# openSX70_ALADDIN_V391_20180125C.net
KiCad netlist of a schematic drawn in EAGLE
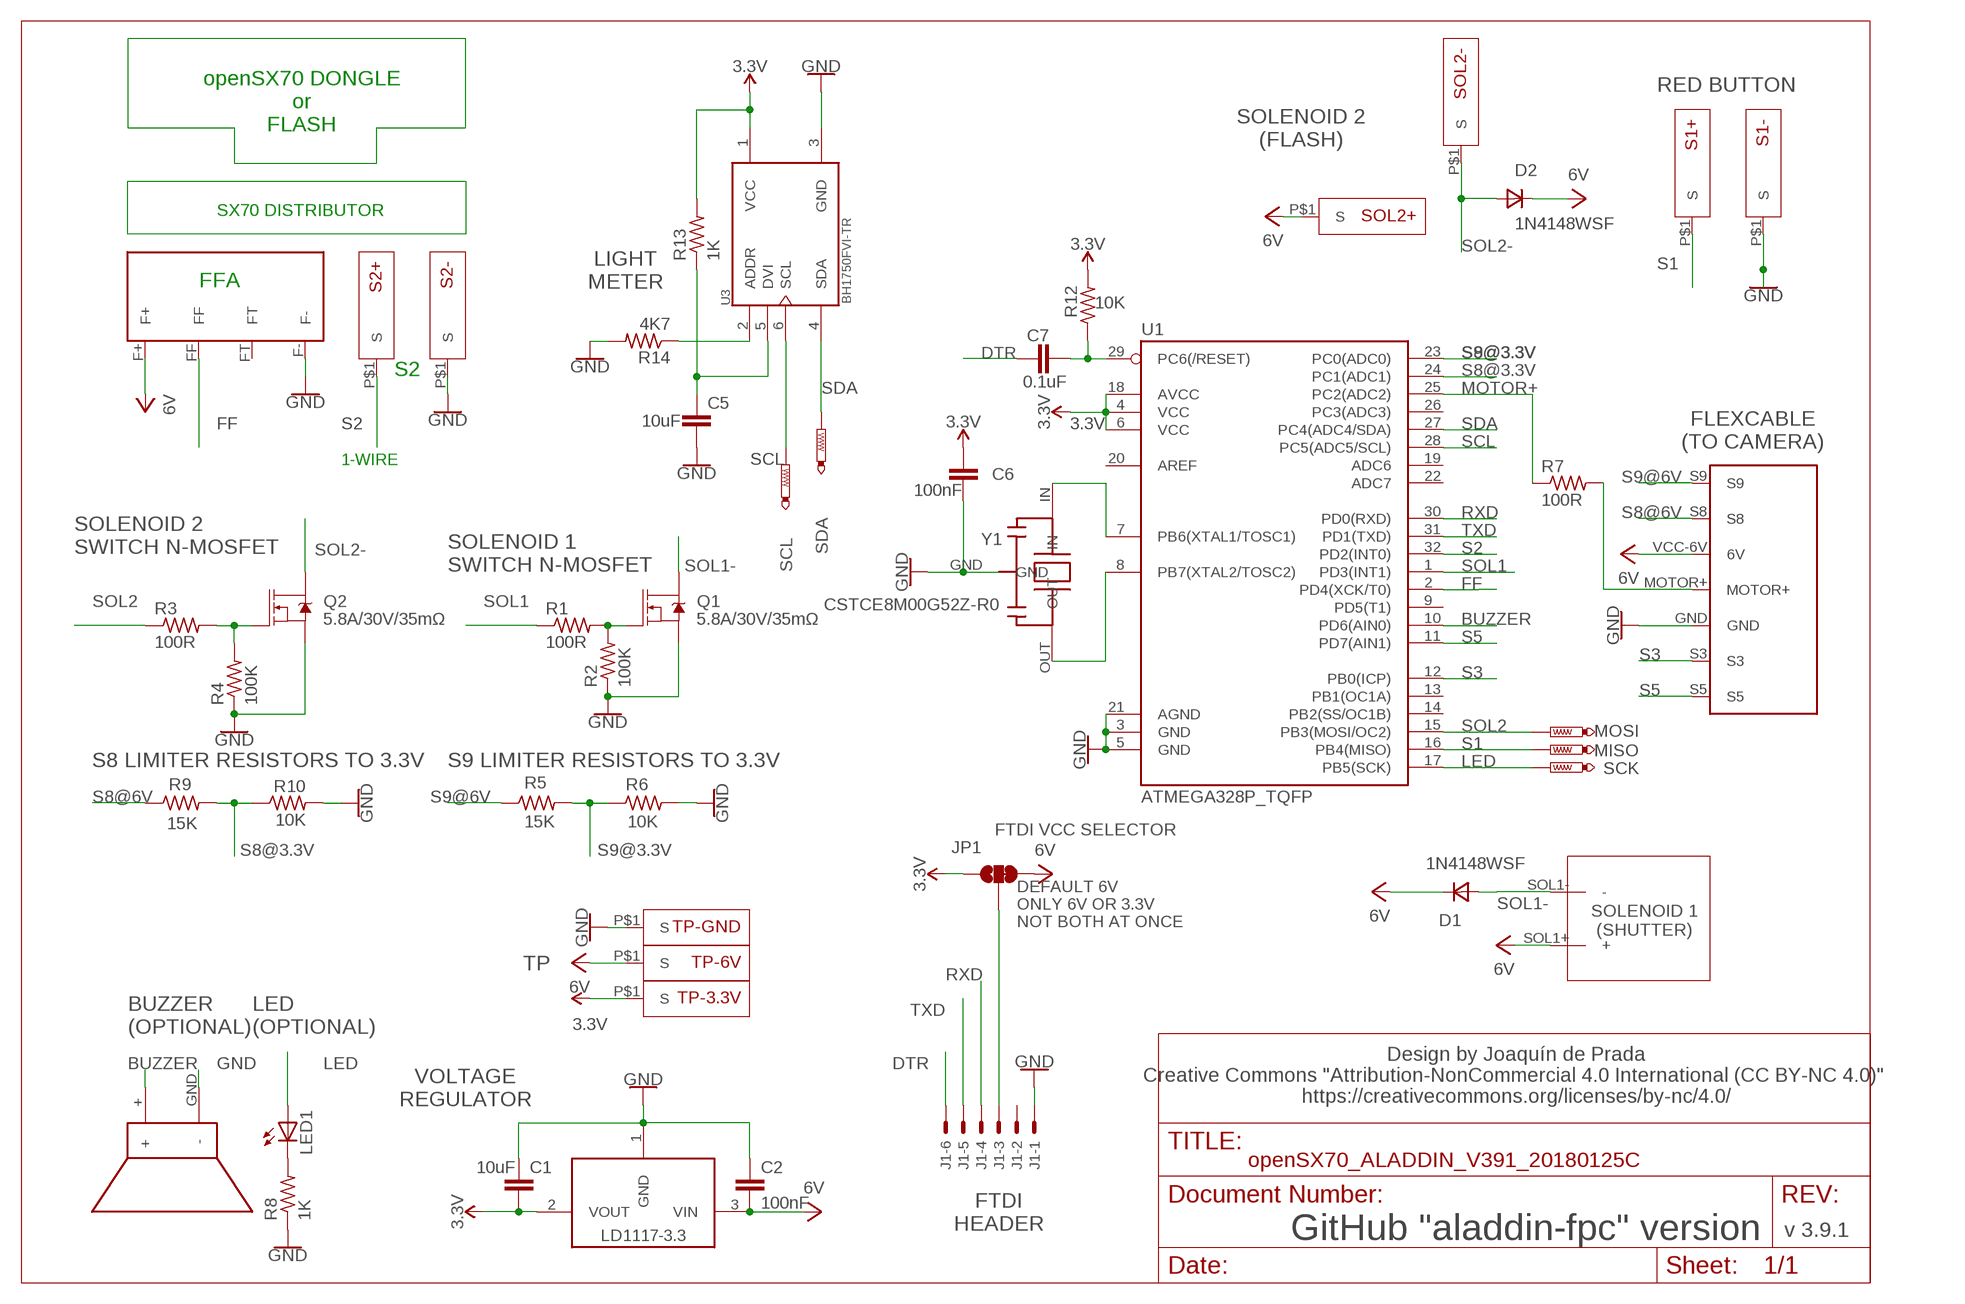
[diagram p0: schematic, sheet 1]

(export (version "E")
  (design (tool "Eeschema 10.0.6"))
  (components
    (comp (ref "BUZZ1")
      (value "CSET8-5G")
      (footprint "eagle-import:CSET8-5G_PACKAGE")
      (libsource (lib "eagle-import") (part "CSET8-5G"))
    )
    (comp (ref "C1")
      (value "10uF")
      (footprint "eagle-import:0603")
      (libsource (lib "eagle-import") (part "10UF-0603-6.3V-20%"))
    )
    (comp (ref "C2")
      (value "100nF")
      (footprint "eagle-import:C0603K")
      (libsource (lib "eagle-import") (part "C-EUC0603K"))
    )
    (comp (ref "C5")
      (value "10uF")
      (footprint "eagle-import:0603")
      (libsource (lib "eagle-import") (part "10UF-0603-6.3V-20%"))
    )
    (comp (ref "C6")
      (value "100nF")
      (footprint "eagle-import:C0603")
      (libsource (lib "eagle-import") (part "C-EUC0603"))
    )
    (comp (ref "C7")
      (value "0.1uF")
      (footprint "eagle-import:0603")
      (libsource (lib "eagle-import") (part "0.1UF-0603-25V-(+80/-20%)"))
    )
    (comp (ref "D1")
      (value "1N4148WSF")
      (footprint "eagle-import:SOD323")
      (fields (field (name "MPN") "CDSOD323-T05C"))
      (libsource (lib "eagle-import") (part "DSOD323"))
    )
    (comp (ref "D2")
      (value "1N4148WSF")
      (footprint "eagle-import:SOD323")
      (fields (field (name "MPN") "CDSOD323-T05C"))
      (libsource (lib "eagle-import") (part "DSOD323"))
    )
    (comp (ref "J1")
      (value "GND")
      (footprint "eagle-import:XF2L-0625-1")
      (fields (field (name "MF") "OMRON COMPONENTS USA") (field (name "MPN") "XF2L-0625-1"))
      (libsource (lib "eagle-import") (part "XF2-06?25-1L"))
    )
    (comp (ref "JP1")
      (value "FTDI VCC SELECTOR")
      (footprint "eagle-import:SMT-JUMPER_3_1-NC_TRACE_SILK")
      (libsource (lib "eagle-import") (part "JUMPER-SMT_3_1-NC_TRACE_SILK"))
    )
    (comp (ref "LD11172.5V")
      (value "LD1117 2.5V")
      (footprint "eagle-import:SOT223")
      (fields (field (name "MF") "Advanced Monolithic Systems") (field (name "MP") "AMS1117-5.0"))
      (libsource (lib "eagle-import") (part "LD1117-3.3"))
    )
    (comp (ref "LED1")
      (value "LEDCHIPLED_0805")
      (footprint "eagle-import:CHIPLED_0805")
      (libsource (lib "eagle-import") (part "LEDCHIPLED_0805"))
    )
    (comp (ref "MISO")
      (value "PTR1TP08R")
      (footprint "eagle-import:TP08R")
      (libsource (lib "eagle-import") (part "PTR1TP08R"))
    )
    (comp (ref "MOSI")
      (value "PTR1TP08R")
      (footprint "eagle-import:TP08R")
      (libsource (lib "eagle-import") (part "PTR1TP08R"))
    )
    (comp (ref "Q1")
      (value "5.8A/30V/35mΩ")
      (footprint "eagle-import:SOT23-3")
      (libsource (lib "eagle-import") (part "MOSFET-NCH-AO3404A"))
    )
    (comp (ref "Q2")
      (value "5.8A/30V/35mΩ")
      (footprint "eagle-import:SOT23-3")
      (libsource (lib "eagle-import") (part "MOSFET-NCH-AO3404A"))
    )
    (comp (ref "R1")
      (value "100R")
      (footprint "eagle-import:R0603")
      (libsource (lib "eagle-import") (part "R-US_R0603"))
    )
    (comp (ref "R2")
      (value "100K")
      (footprint "eagle-import:R0603")
      (libsource (lib "eagle-import") (part "R-US_R0603"))
    )
    (comp (ref "R3")
      (value "100R")
      (footprint "eagle-import:R0603")
      (libsource (lib "eagle-import") (part "R-US_R0603"))
    )
    (comp (ref "R4")
      (value "100K")
      (footprint "eagle-import:R0603")
      (libsource (lib "eagle-import") (part "R-US_R0603"))
    )
    (comp (ref "R5")
      (value "15K")
      (footprint "eagle-import:R0603")
      (libsource (lib "eagle-import") (part "R-US_R0603"))
    )
    (comp (ref "R6")
      (value "10K")
      (footprint "eagle-import:R0603")
      (libsource (lib "eagle-import") (part "R-US_R0603"))
    )
    (comp (ref "R7")
      (value "100R")
      (footprint "eagle-import:R0603")
      (libsource (lib "eagle-import") (part "R-US_R0603"))
    )
    (comp (ref "R8")
      (value "1K")
      (footprint "eagle-import:R0603")
      (libsource (lib "eagle-import") (part "R-US_R0603"))
    )
    (comp (ref "R9")
      (value "15K")
      (footprint "eagle-import:R0603")
      (libsource (lib "eagle-import") (part "R-US_R0603"))
    )
    (comp (ref "R10")
      (value "10K")
      (footprint "eagle-import:R0603")
      (libsource (lib "eagle-import") (part "R-US_R0603"))
    )
    (comp (ref "R12")
      (value "10K")
      (footprint "eagle-import:R0603")
      (libsource (lib "eagle-import") (part "R-US_R0603"))
    )
    (comp (ref "R13")
      (value "1K")
      (footprint "eagle-import:R0603")
      (libsource (lib "eagle-import") (part "R-US_R0603"))
    )
    (comp (ref "R14")
      (value "4K7")
      (footprint "eagle-import:R0603")
      (libsource (lib "eagle-import") (part "R-US_R0603"))
    )
    (comp (ref "S1+")
      (value "SX70-S-PAD-NEW")
      (footprint "eagle-import:SX70-S-PAD2")
      (libsource (lib "eagle-import") (part "SX70-S-PAD-NEW"))
    )
    (comp (ref "S1-")
      (value "SX70-S-PAD-NEW")
      (footprint "eagle-import:SX70-S-PAD2")
      (libsource (lib "eagle-import") (part "SX70-S-PAD-NEW"))
    )
    (comp (ref "S2+")
      (value "SX70-S-PAD-NEW")
      (footprint "eagle-import:SX70-S-PAD2")
      (libsource (lib "eagle-import") (part "SX70-S-PAD-NEW"))
    )
    (comp (ref "S2-")
      (value "SX70-S-PAD-NEW")
      (footprint "eagle-import:SX70-S-PAD2")
      (libsource (lib "eagle-import") (part "SX70-S-PAD-NEW"))
    )
    (comp (ref "SCK")
      (value "PTR1TP08R")
      (footprint "eagle-import:TP08R")
      (libsource (lib "eagle-import") (part "PTR1TP08R"))
    )
    (comp (ref "SCL")
      (value "PTR1TP08R")
      (footprint "eagle-import:TP08R")
      (libsource (lib "eagle-import") (part "PTR1TP08R"))
    )
    (comp (ref "SDA")
      (value "PTR1TP08R")
      (footprint "eagle-import:TP08R")
      (libsource (lib "eagle-import") (part "PTR1TP08R"))
    )
    (comp (ref "SOL1")
      (value "SX70-SOLENOID1-2PADS")
      (footprint "eagle-import:SX70-SOLENOID1-2")
      (libsource (lib "eagle-import") (part "SX70-SOLENOID1-2PADS"))
    )
    (comp (ref "SOL2+")
      (value "SX70-S-PAD-NEW")
      (footprint "eagle-import:SX70-S-PAD2")
      (libsource (lib "eagle-import") (part "SX70-S-PAD-NEW"))
    )
    (comp (ref "SOL2-")
      (value "SX70-S-PAD-NEW")
      (footprint "eagle-import:SX70-S-PAD2")
      (libsource (lib "eagle-import") (part "SX70-S-PAD-NEW"))
    )
    (comp (ref "TP-3.3V")
      (value "SX70-S-PAD-NEW")
      (footprint "eagle-import:SX70-S-PAD2")
      (libsource (lib "eagle-import") (part "SX70-S-PAD-NEW"))
    )
    (comp (ref "TP-6V")
      (value "SX70-S-PAD-NEW")
      (footprint "eagle-import:SX70-S-PAD2")
      (libsource (lib "eagle-import") (part "SX70-S-PAD-NEW"))
    )
    (comp (ref "TP-GND")
      (value "SX70-S-PAD-NEW")
      (footprint "eagle-import:SX70-S-PAD2")
      (libsource (lib "eagle-import") (part "SX70-S-PAD-NEW"))
    )
    (comp (ref "U$1")
      (value "SX70-7-PAD")
      (footprint "eagle-import:SX70-7-PAD")
      (libsource (lib "eagle-import") (part "SX70-7-PAD"))
    )
    (comp (ref "U$2")
      (value "FFA")
      (footprint "eagle-import:FFA-PAD-PACKAGE")
      (libsource (lib "eagle-import") (part "SX70-FFA-PAD"))
    )
    (comp (ref "U1")
      (value "ATMEGA328P_TQFP")
      (footprint "eagle-import:TQFP32-08")
      (libsource (lib "eagle-import") (part "ATMEGA328P_TQFP"))
    )
    (comp (ref "U3")
      (value "BH1750FVI-TR")
      (footprint "eagle-import:SOTFL50P300X75-6N")
      (fields (field (name "MF") "Rohm"))
      (libsource (lib "eagle-import") (part "BH1750FVI-TR"))
    )
    (comp (ref "Y1")
      (value "CSTCE8M00G52Z-R0")
      (footprint "eagle-import:CFP95P160X100-3N")
      (fields (field (name "MF") "Murata") (field (name "MP") "CSTCE16M0V53-R0"))
      (libsource (lib "eagle-import") (part "CSTCE16M0V53-R0"))
    )
  )
  (nets
    (net (code "1") (name "/BUZZER") (class "Default")
      (node (ref "BUZZ1") (pin "+") (pinfunction "+_+") (pintype "bidirectional"))
      (node (ref "U1") (pin "10") (pinfunction "PD6(AIN0)_10") (pintype "bidirectional"))
    )
    (net (code "2") (name "/DTR") (class "Default")
      (node (ref "C7") (pin "1") (pinfunction "1_1") (pintype "passive"))
      (node (ref "J1") (pin "6") (pinfunction "MS_6") (pintype "passive"))
    )
    (net (code "3") (name "/FF") (class "Default")
      (node (ref "U$2") (pin "FF") (pinfunction "FF_FF") (pintype "bidirectional"))
      (node (ref "U1") (pin "2") (pinfunction "PD4(XCK/T0)_2") (pintype "bidirectional"))
    )
    (net (code "4") (name "/LED") (class "Default")
      (node (ref "LED1") (pin "A") (pinfunction "A_A") (pintype "passive"))
      (node (ref "SCK") (pin "TP") (pinfunction "TP_TP") (pintype "input"))
      (node (ref "U1") (pin "17") (pinfunction "PB5(SCK)_17") (pintype "bidirectional"))
    )
    (net (code "5") (name "/MOTOR+") (class "Default")
      (node (ref "R7") (pin "1") (pinfunction "1_1") (pintype "passive"))
      (node (ref "U1") (pin "25") (pinfunction "PC2(ADC2)_25") (pintype "bidirectional"))
    )
    (net (code "6") (name "/RXD") (class "Default")
      (node (ref "J1") (pin "4") (pinfunction "MS_4") (pintype "passive"))
      (node (ref "U1") (pin "30") (pinfunction "PD0(RXD)_30") (pintype "bidirectional"))
    )
    (net (code "7") (name "/S1") (class "Default")
      (node (ref "MISO") (pin "TP") (pinfunction "TP_TP") (pintype "input"))
      (node (ref "S1+") (pin "P$1") (pinfunction "S_P$1") (pintype "bidirectional"))
      (node (ref "U1") (pin "16") (pinfunction "PB4(MISO)_16") (pintype "bidirectional"))
    )
    (net (code "8") (name "/S2") (class "Default")
      (node (ref "S2+") (pin "P$1") (pinfunction "S_P$1") (pintype "bidirectional"))
      (node (ref "U1") (pin "32") (pinfunction "PD2(INT0)_32") (pintype "bidirectional"))
    )
    (net (code "9") (name "/S3") (class "Default")
      (node (ref "U$1") (pin "S3") (pinfunction "S3_S3") (pintype "bidirectional"))
      (node (ref "U1") (pin "12") (pinfunction "PB0(ICP)_12") (pintype "bidirectional"))
    )
    (net (code "10") (name "/S5") (class "Default")
      (node (ref "U$1") (pin "S5") (pinfunction "S5_S5") (pintype "bidirectional"))
      (node (ref "U1") (pin "11") (pinfunction "PD7(AIN1)_11") (pintype "bidirectional"))
    )
    (net (code "11") (name "/S8@3.3V") (class "Default")
      (node (ref "R10") (pin "1") (pinfunction "1_1") (pintype "passive"))
      (node (ref "R9") (pin "2") (pinfunction "2_2") (pintype "passive"))
      (node (ref "U1") (pin "24") (pinfunction "PC1(ADC1)_24") (pintype "bidirectional"))
    )
    (net (code "12") (name "/S8@6V") (class "Default")
      (node (ref "R9") (pin "1") (pinfunction "1_1") (pintype "passive"))
      (node (ref "U$1") (pin "S8") (pinfunction "S8_S8") (pintype "bidirectional"))
    )
    (net (code "13") (name "/S9@3.3V") (class "Default")
      (node (ref "R5") (pin "2") (pinfunction "2_2") (pintype "passive"))
      (node (ref "R6") (pin "1") (pinfunction "1_1") (pintype "passive"))
      (node (ref "U1") (pin "23") (pinfunction "PC0(ADC0)_23") (pintype "bidirectional"))
    )
    (net (code "14") (name "/S9@6V") (class "Default")
      (node (ref "R5") (pin "1") (pinfunction "1_1") (pintype "passive"))
      (node (ref "U$1") (pin "S9") (pinfunction "S9_S9") (pintype "bidirectional"))
    )
    (net (code "15") (name "/SCL") (class "Default")
      (node (ref "SCL") (pin "TP") (pinfunction "TP_TP") (pintype "input"))
      (node (ref "U1") (pin "28") (pinfunction "PC5(ADC5/SCL)_28") (pintype "bidirectional"))
      (node (ref "U3") (pin "6") (pinfunction "SCL_6") (pintype "input"))
    )
    (net (code "16") (name "/SDA") (class "Default")
      (node (ref "SDA") (pin "TP") (pinfunction "TP_TP") (pintype "input"))
      (node (ref "U1") (pin "27") (pinfunction "PC4(ADC4/SDA)_27") (pintype "bidirectional"))
      (node (ref "U3") (pin "4") (pinfunction "SDA_4") (pintype "bidirectional"))
    )
    (net (code "17") (name "/SOL1") (class "Default")
      (node (ref "R1") (pin "1") (pinfunction "1_1") (pintype "passive"))
      (node (ref "U1") (pin "1") (pinfunction "PD3(INT1)_1") (pintype "bidirectional"))
    )
    (net (code "18") (name "/SOL1-") (class "Default")
      (node (ref "D1") (pin "2") (pinfunction "A_2") (pintype "passive"))
      (node (ref "Q1") (pin "3") (pinfunction "D_3") (pintype "bidirectional"))
      (node (ref "SOL1") (pin "SOL1-") (pinfunction "-_SOL1-") (pintype "bidirectional"))
    )
    (net (code "19") (name "/SOL2") (class "Default")
      (node (ref "MOSI") (pin "TP") (pinfunction "TP_TP") (pintype "input"))
      (node (ref "R3") (pin "1") (pinfunction "1_1") (pintype "passive"))
      (node (ref "U1") (pin "15") (pinfunction "PB3(MOSI/OC2)_15") (pintype "bidirectional"))
    )
    (net (code "20") (name "/SOL2-") (class "Default")
      (node (ref "D2") (pin "2") (pinfunction "A_2") (pintype "passive"))
      (node (ref "Q2") (pin "3") (pinfunction "D_3") (pintype "bidirectional"))
      (node (ref "SOL2-") (pin "P$1") (pinfunction "S_P$1") (pintype "bidirectional"))
    )
    (net (code "21") (name "/TXD") (class "Default")
      (node (ref "J1") (pin "5") (pinfunction "MS_5") (pintype "passive"))
      (node (ref "U1") (pin "31") (pinfunction "PD1(TXD)_31") (pintype "bidirectional"))
    )
    (net (code "22") (name "3.3V") (class "Default")
      (node (ref "C1") (pin "2") (pinfunction "2_2") (pintype "passive"))
      (node (ref "C6") (pin "1") (pinfunction "1_1") (pintype "passive"))
      (node (ref "JP1") (pin "1") (pinfunction "1_1") (pintype "passive"))
      (node (ref "LD11172.5V") (pin "2") (pinfunction "VOUT_2") (pintype "bidirectional"))
      (node (ref "R12") (pin "2") (pinfunction "2_2") (pintype "passive"))
      (node (ref "R13") (pin "2") (pinfunction "2_2") (pintype "passive"))
      (node (ref "TP-3.3V") (pin "P$1") (pinfunction "S_P$1") (pintype "bidirectional"))
      (node (ref "U1") (pin "18") (pinfunction "AVCC_18") (pintype "bidirectional"))
      (node (ref "U1") (pin "4") (pinfunction "VCC_4") (pintype "bidirectional"))
      (node (ref "U1") (pin "6") (pinfunction "VCC_6") (pintype "bidirectional"))
      (node (ref "U3") (pin "1") (pinfunction "VCC_1") (pintype "power_in"))
    )
    (net (code "23") (name "6V") (class "Default")
      (node (ref "C2") (pin "2") (pinfunction "2_2") (pintype "passive"))
      (node (ref "D1") (pin "1") (pinfunction "C_1") (pintype "passive"))
      (node (ref "D2") (pin "1") (pinfunction "C_1") (pintype "passive"))
      (node (ref "JP1") (pin "3") (pinfunction "3_3") (pintype "passive"))
      (node (ref "LD11172.5V") (pin "3") (pinfunction "VIN_3") (pintype "bidirectional"))
      (node (ref "SOL1") (pin "SOL1+") (pinfunction "+_SOL1+") (pintype "bidirectional"))
      (node (ref "SOL2+") (pin "P$1") (pinfunction "S_P$1") (pintype "bidirectional"))
      (node (ref "TP-6V") (pin "P$1") (pinfunction "S_P$1") (pintype "bidirectional"))
      (node (ref "U$1") (pin "VCC-6V") (pinfunction "6V_VCC-6V") (pintype "bidirectional"))
      (node (ref "U$2") (pin "F+") (pinfunction "F+_F+") (pintype "bidirectional"))
    )
    (net (code "24") (name "GND") (class "Default")
      (node (ref "BUZZ1") (pin "GND") (pinfunction "-_GND") (pintype "bidirectional"))
      (node (ref "C1") (pin "1") (pinfunction "1_1") (pintype "passive"))
      (node (ref "C2") (pin "1") (pinfunction "1_1") (pintype "passive"))
      (node (ref "C5") (pin "2") (pinfunction "2_2") (pintype "passive"))
      (node (ref "C6") (pin "2") (pinfunction "2_2") (pintype "passive"))
      (node (ref "J1") (pin "1") (pinfunction "MS_1") (pintype "passive"))
      (node (ref "LD11172.5V") (pin "1") (pinfunction "GND_1") (pintype "bidirectional"))
      (node (ref "Q1") (pin "2") (pinfunction "S_2") (pintype "bidirectional"))
      (node (ref "Q2") (pin "2") (pinfunction "S_2") (pintype "bidirectional"))
      (node (ref "R10") (pin "2") (pinfunction "2_2") (pintype "passive"))
      (node (ref "R14") (pin "2") (pinfunction "2_2") (pintype "passive"))
      (node (ref "R2") (pin "1") (pinfunction "1_1") (pintype "passive"))
      (node (ref "R4") (pin "1") (pinfunction "1_1") (pintype "passive"))
      (node (ref "R6") (pin "2") (pinfunction "2_2") (pintype "passive"))
      (node (ref "R8") (pin "1") (pinfunction "1_1") (pintype "passive"))
      (node (ref "S1-") (pin "P$1") (pinfunction "S_P$1") (pintype "bidirectional"))
      (node (ref "S2-") (pin "P$1") (pinfunction "S_P$1") (pintype "bidirectional"))
      (node (ref "TP-GND") (pin "P$1") (pinfunction "S_P$1") (pintype "bidirectional"))
      (node (ref "U$1") (pin "GND") (pinfunction "GND_GND") (pintype "bidirectional"))
      (node (ref "U$2") (pin "F-") (pinfunction "F-_F-") (pintype "bidirectional"))
      (node (ref "U1") (pin "21") (pinfunction "AGND_21") (pintype "bidirectional"))
      (node (ref "U1") (pin "3") (pinfunction "GND_3") (pintype "bidirectional"))
      (node (ref "U1") (pin "5") (pinfunction "GND_5") (pintype "bidirectional"))
      (node (ref "U3") (pin "3") (pinfunction "GND_3") (pintype "power_in"))
      (node (ref "Y1") (pin "GND") (pinfunction "GND_GND") (pintype "passive"))
    )
    (net (code "25") (name "Net-(J1C-MS)") (class "Default")
      (node (ref "J1") (pin "3") (pinfunction "MS_3") (pintype "passive"))
      (node (ref "JP1") (pin "2") (pinfunction "2_2") (pintype "passive"))
    )
    (net (code "26") (name "Net-(LED1-PadC)") (class "Default")
      (node (ref "LED1") (pin "C") (pinfunction "C_C") (pintype "passive"))
      (node (ref "R8") (pin "2") (pinfunction "2_2") (pintype "passive"))
    )
    (net (code "27") (name "Net-(Q1-G)") (class "Default")
      (node (ref "Q1") (pin "1") (pinfunction "G_1") (pintype "bidirectional"))
      (node (ref "R1") (pin "2") (pinfunction "2_2") (pintype "passive"))
      (node (ref "R2") (pin "2") (pinfunction "2_2") (pintype "passive"))
    )
    (net (code "28") (name "Net-(Q2-G)") (class "Default")
      (node (ref "Q2") (pin "1") (pinfunction "G_1") (pintype "bidirectional"))
      (node (ref "R3") (pin "2") (pinfunction "2_2") (pintype "passive"))
      (node (ref "R4") (pin "2") (pinfunction "2_2") (pintype "passive"))
    )
    (net (code "29") (name "Net-(R7-Pad2)") (class "Default")
      (node (ref "R7") (pin "2") (pinfunction "2_2") (pintype "passive"))
      (node (ref "U$1") (pin "MOTOR+") (pinfunction "MOTOR+_MOTOR+") (pintype "bidirectional"))
    )
    (net (code "30") (name "Net-(U1-PB6(XTAL1{slash}TOSC1))") (class "Default")
      (node (ref "U1") (pin "7") (pinfunction "PB6(XTAL1/TOSC1)_7") (pintype "bidirectional"))
      (node (ref "Y1") (pin "IN") (pinfunction "IN_IN") (pintype "input"))
    )
    (net (code "31") (name "Net-(U1-PB7(XTAL2{slash}TOSC2))") (class "Default")
      (node (ref "U1") (pin "8") (pinfunction "PB7(XTAL2/TOSC2)_8") (pintype "bidirectional"))
      (node (ref "Y1") (pin "OUT") (pinfunction "OUT_OUT") (pintype "output"))
    )
    (net (code "32") (name "Net-(U1-PC6({slash}RESET))") (class "Default")
      (node (ref "C7") (pin "2") (pinfunction "2_2") (pintype "passive"))
      (node (ref "R12") (pin "1") (pinfunction "1_1") (pintype "passive"))
      (node (ref "U1") (pin "29") (pinfunction "PC6(/RESET)_29") (pintype "bidirectional"))
    )
    (net (code "33") (name "Net-(U3-ADDR)") (class "Default")
      (node (ref "R14") (pin "1") (pinfunction "1_1") (pintype "passive"))
      (node (ref "U3") (pin "2") (pinfunction "ADDR_2") (pintype "input"))
    )
    (net (code "34") (name "Net-(U3-DVI)") (class "Default")
      (node (ref "C5") (pin "1") (pinfunction "1_1") (pintype "passive"))
      (node (ref "R13") (pin "1") (pinfunction "1_1") (pintype "passive"))
      (node (ref "U3") (pin "5") (pinfunction "DVI_5") (pintype "input"))
    )
    (net (code "35") (name "unconnected-(J1B-MS-Pad2)") (class "Default")
      (node (ref "J1") (pin "2") (pinfunction "MS_2") (pintype "passive"))
    )
    (net (code "36") (name "unconnected-(U$2-PadFT)") (class "Default")
      (node (ref "U$2") (pin "FT") (pinfunction "FT_FT") (pintype "bidirectional"))
    )
    (net (code "37") (name "unconnected-(U1-ADC6-Pad19)") (class "Default")
      (node (ref "U1") (pin "19") (pinfunction "ADC6_19") (pintype "bidirectional"))
    )
    (net (code "38") (name "unconnected-(U1-ADC7-Pad22)") (class "Default")
      (node (ref "U1") (pin "22") (pinfunction "ADC7_22") (pintype "bidirectional"))
    )
    (net (code "39") (name "unconnected-(U1-AREF-Pad20)") (class "Default")
      (node (ref "U1") (pin "20") (pinfunction "AREF_20") (pintype "bidirectional"))
    )
    (net (code "40") (name "unconnected-(U1-PB1(OC1A)-Pad13)") (class "Default")
      (node (ref "U1") (pin "13") (pinfunction "PB1(OC1A)_13") (pintype "bidirectional"))
    )
    (net (code "41") (name "unconnected-(U1-PB2(SS{slash}OC1B)-Pad14)") (class "Default")
      (node (ref "U1") (pin "14") (pinfunction "PB2(SS/OC1B)_14") (pintype "bidirectional"))
    )
    (net (code "42") (name "unconnected-(U1-PC3(ADC3)-Pad26)") (class "Default")
      (node (ref "U1") (pin "26") (pinfunction "PC3(ADC3)_26") (pintype "bidirectional"))
    )
    (net (code "43") (name "unconnected-(U1-PD5(T1)-Pad9)") (class "Default")
      (node (ref "U1") (pin "9") (pinfunction "PD5(T1)_9") (pintype "bidirectional"))
    )
  )
)
